# Atmega-SolderingStation-v2_7_2025-10-03.net
KiCad netlist of a schematic drawn in Altium Designer
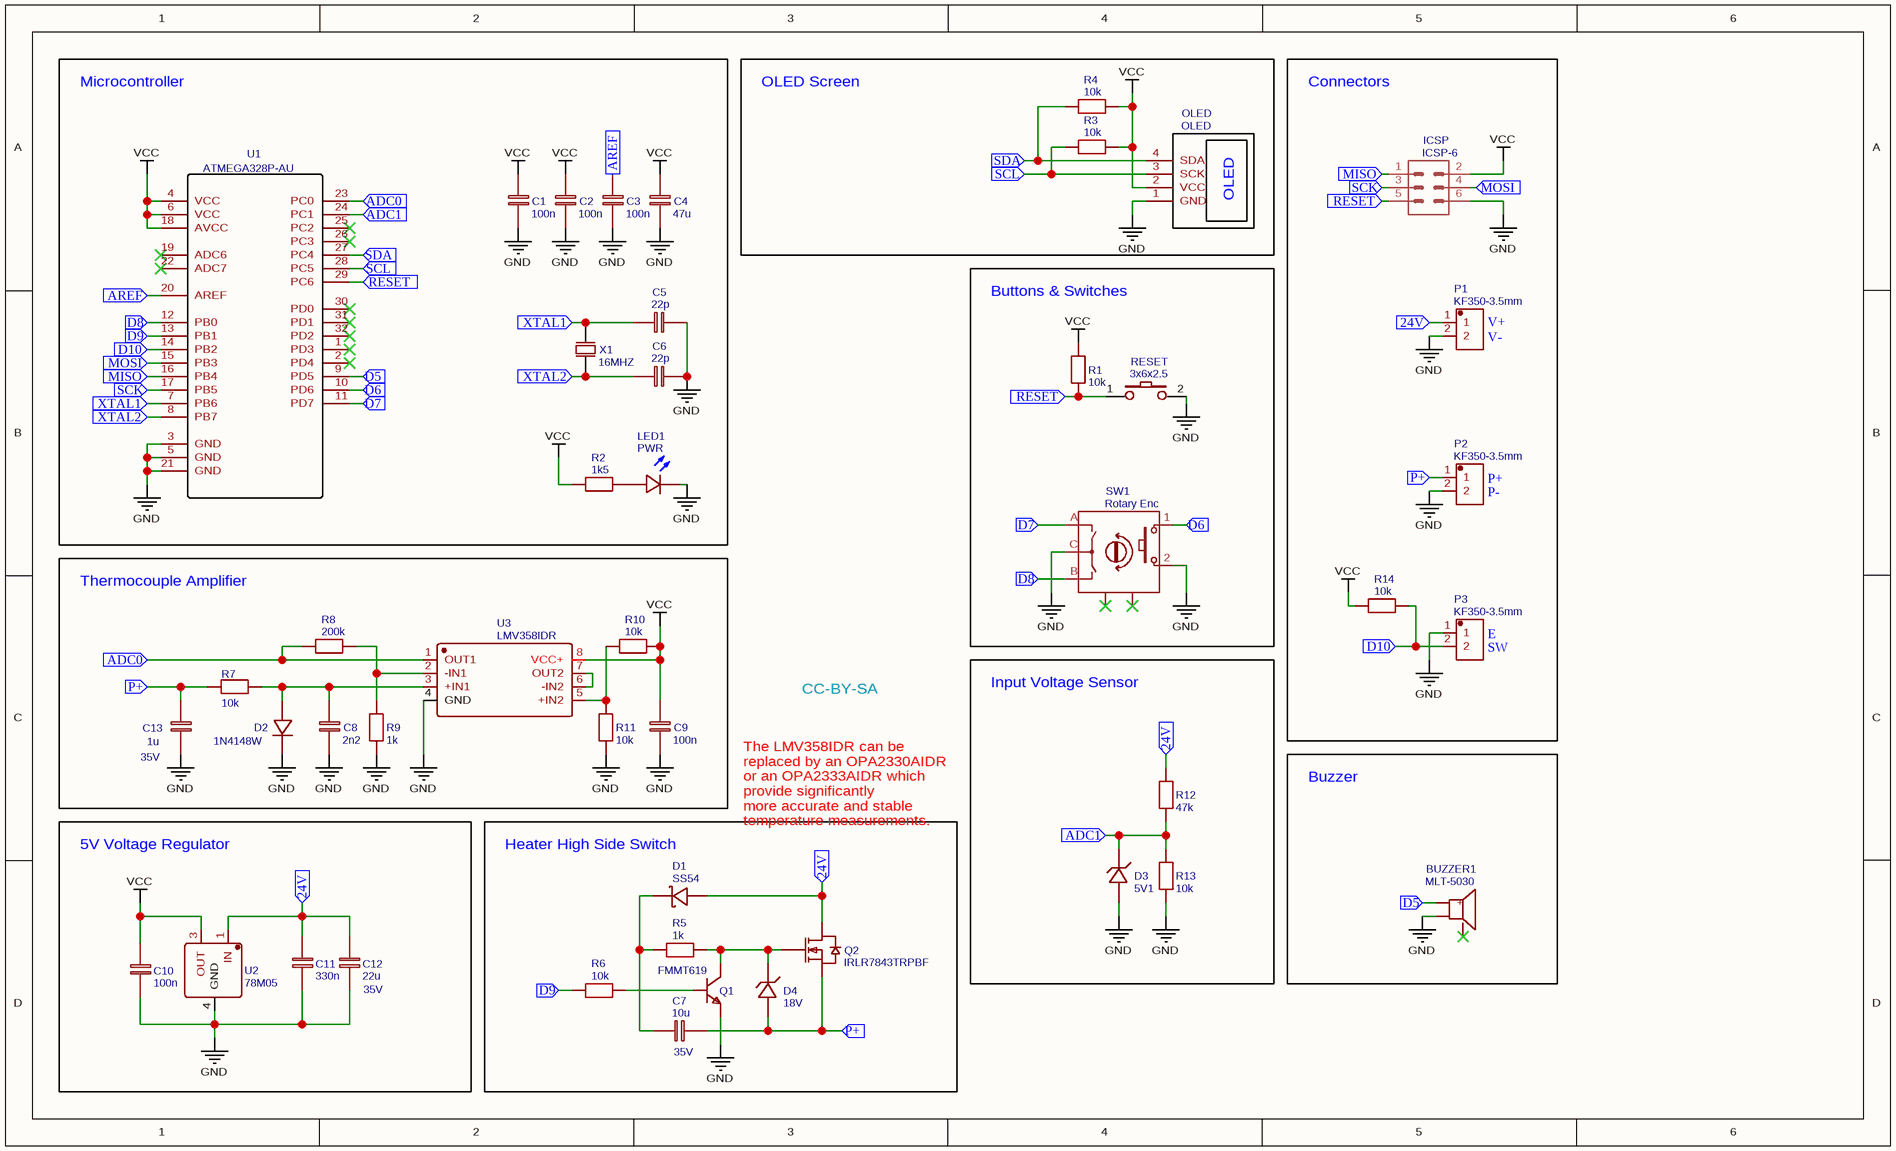
[diagram p0: Atmega-SolderingStation-v2.7_2025-10-03.schdoc]

(export (version "E")
  (design (tool "Eeschema 10.0.6"))
  (components
    (comp (ref "BUZZER1")
      (value "MLT-5030")
      (fields (field (name "MANUFACTURER") "HNDZ"))
      (libsource (lib "altium-import") (part "root_0_MLT-5030_"))
    )
    (comp (ref "C1")
      (value "100n")
      (fields (field (name "MANUFACTURER PART") "CC0603KRX7R9BB104") (field (name "MANUFACTURER") "YAGEO"))
      (libsource (lib "altium-import") (part "root_0_100n_"))
    )
    (comp (ref "C2")
      (value "100n")
      (fields (field (name "MANUFACTURER PART") "CC0603KRX7R9BB104") (field (name "MANUFACTURER") "YAGEO"))
      (libsource (lib "altium-import") (part "root_0_100n_"))
    )
    (comp (ref "C3")
      (value "100n")
      (fields (field (name "MANUFACTURER PART") "CC0603KRX7R9BB104") (field (name "MANUFACTURER") "YAGEO"))
      (libsource (lib "altium-import") (part "root_0_100n_"))
    )
    (comp (ref "C4")
      (value "47u")
      (fields (field (name "MANUFACTURER PART") "1206F476M100NT") (field (name "MANUFACTURER") "FH"))
      (libsource (lib "altium-import") (part "root_0_47u_"))
    )
    (comp (ref "C5")
      (value "22p")
      (fields (field (name "MANUFACTURER PART") "CL10C220JB8NNNC") (field (name "MANUFACTURER") "SAMSUNG"))
      (libsource (lib "altium-import") (part "root_1_22p_"))
    )
    (comp (ref "C6")
      (value "22p")
      (fields (field (name "MANUFACTURER PART") "CL10C220JB8NNNC") (field (name "MANUFACTURER") "SAMSUNG"))
      (libsource (lib "altium-import") (part "root_1_22p_"))
    )
    (comp (ref "C7")
      (value "10u")
      (fields
        (field (name "MANUFACTURER PART") "GMK316BJ106KL-T")
        (field (name "MANUFACTURER") "Taiyo Yuden")
      )
      (libsource (lib "altium-import") (part "root_1_10u_"))
    )
    (comp (ref "C8")
      (value "2n2")
      (fields (field (name "MANUFACTURER PART") "0603B222K500NT") (field (name "MANUFACTURER") "FH"))
      (libsource (lib "altium-import") (part "root_0_2n2_"))
    )
    (comp (ref "C9")
      (value "100n")
      (fields (field (name "MANUFACTURER PART") "CC0603KRX7R9BB104") (field (name "MANUFACTURER") "YAGEO"))
      (libsource (lib "altium-import") (part "root_0_100n_"))
    )
    (comp (ref "C10")
      (value "100n")
      (fields (field (name "MANUFACTURER PART") "CC0603KRX7R9BB104") (field (name "MANUFACTURER") "YAGEO"))
      (libsource (lib "altium-import") (part "root_0_100n_"))
    )
    (comp (ref "C11")
      (value "330n")
      (fields (field (name "MANUFACTURER PART") "C1608X7R1H334KT000E") (field (name "MANUFACTURER") "TDK"))
      (libsource (lib "altium-import") (part "root_0_330n_"))
    )
    (comp (ref "C12")
      (value "22u")
      (fields (field (name "MANUFACTURER PART") "C3216X5R1V226MTJ00E") (field (name "MANUFACTURER") "TDK"))
      (libsource (lib "altium-import") (part "root_0_22u_"))
    )
    (comp (ref "C13")
      (value "1u")
      (fields (field (name "MANUFACTURER PART") "CL10A105KB8NNNC") (field (name "MANUFACTURER") "SAMSUNG"))
      (libsource (lib "altium-import") (part "root_0_1u_"))
    )
    (comp (ref "D1")
      (value "SS54")
      (fields (field (name "MANUFACTURER") "Jingdao") (field (name "CONTRIBUTOR") "LCSC"))
      (libsource (lib "altium-import") (part "root_0_SS54_"))
    )
    (comp (ref "D2")
      (value "1N4148W")
      (fields
        (field (name "MANUFACTURER") "Vishay Intertech")
        (field (name "MANUFACTURER PART") "1N4148W-E3-08")
        (field (name "CONTRIBUTOR") "LCSC")
      )
      (libsource (lib "altium-import") (part "root_3_1N4148W_"))
    )
    (comp (ref "D3")
      (value "5V1")
      (fields
        (field (name "MANUFACTURER") "SEMTECH")
        (field (name "MANUFACTURER PART") "MM1Z5V1")
        (field (name "CONTRIBUTOR") "LCSC")
      )
      (libsource (lib "altium-import") (part "root_1_5V1_"))
    )
    (comp (ref "D4")
      (value "18V")
      (fields
        (field (name "MANUFACTURER") "Jingdao")
        (field (name "MANUFACTURER PART") "MM1Z18")
        (field (name "CONTRIBUTOR") "LCSC")
      )
      (libsource (lib "altium-import") (part "root_1_18V_"))
    )
    (comp (ref "ICSP")
      (value "ICSP-6")
      (fields (field (name "MANUFACTURER PART") "?") (field (name "CONTRIBUTOR") "DowntownCB"))
      (libsource (lib "altium-import") (part "root_2_ICSP-6_"))
    )
    (comp (ref "LED1")
      (value "PWR")
      (fields
        (field (name "MANUFACTURER") "EVERLIGHT")
        (field (name "MANUFACTURER PART") "19-217/BHC-ZL1M2RY/3T")
      )
      (libsource (lib "altium-import") (part "root_0_PWR_"))
    )
    (comp (ref "OLED")
      (value "OLED")
      (fields (field (name "MANUFACTURER PART") "SSD1306 I2C OLED") (field (name "CONTRIBUTOR") "stozk"))
      (libsource (lib "altium-import") (part "root_1_OLED_"))
    )
    (comp (ref "P1")
      (value "KF350-3.5mm")
      (fields (field (name "MANUFACTURER") "ReliaPro") (field (name "MANUFACTURER PART") "WJ2EDGVC-5.08-2P"))
      (libsource (lib "altium-import") (part "root_0_KF350-3.5mm_"))
    )
    (comp (ref "P2")
      (value "KF350-3.5mm")
      (fields (field (name "MANUFACTURER") "ReliaPro") (field (name "MANUFACTURER PART") "WJ2EDGVC-5.08-2P"))
      (libsource (lib "altium-import") (part "root_0_KF350-3.5mm_"))
    )
    (comp (ref "P3")
      (value "KF350-3.5mm")
      (fields (field (name "MANUFACTURER") "ReliaPro") (field (name "MANUFACTURER PART") "WJ2EDGVC-5.08-2P"))
      (libsource (lib "altium-import") (part "root_0_KF350-3.5mm_"))
    )
    (comp (ref "Q1")
      (value "FMMT619")
      (fields (field (name "MANUFACTURER") "CJ"))
      (libsource (lib "altium-import") (part "root_0_FMMT619_"))
    )
    (comp (ref "Q2")
      (value "IRLR7843TRPBF")
      (fields (field (name "MANUFACTURER") "IR"))
      (libsource (lib "altium-import") (part "root_0_IRLR7843TRPBF_"))
    )
    (comp (ref "R1")
      (value "10k")
      (fields (field (name "MANUFACTURER PART") "0603WAF1002T5E") (field (name "MANUFACTURER") "UniOhm"))
      (libsource (lib "altium-import") (part "root_1_10k_"))
    )
    (comp (ref "R2")
      (value "1k5")
      (fields (field (name "MANUFACTURER PART") "0603WAF1501T5E") (field (name "MANUFACTURER") "UniOhm"))
      (libsource (lib "altium-import") (part "root_0_1k5_"))
    )
    (comp (ref "R3")
      (value "10k")
      (fields (field (name "MANUFACTURER PART") "0603WAF1002T5E") (field (name "MANUFACTURER") "UniOhm"))
      (libsource (lib "altium-import") (part "root_0_10k_"))
    )
    (comp (ref "R4")
      (value "10k")
      (fields (field (name "MANUFACTURER PART") "0603WAF1002T5E") (field (name "MANUFACTURER") "UniOhm"))
      (libsource (lib "altium-import") (part "root_2_10k_"))
    )
    (comp (ref "R5")
      (value "1k")
      (fields (field (name "MANUFACTURER PART") "1206W4F1001T5E") (field (name "MANUFACTURER") "UniOhm"))
      (libsource (lib "altium-import") (part "root_0_1k_"))
    )
    (comp (ref "R6")
      (value "10k")
      (fields (field (name "MANUFACTURER PART") "0603WAF1002T5E") (field (name "MANUFACTURER") "UniOhm"))
      (libsource (lib "altium-import") (part "root_0_10k_"))
    )
    (comp (ref "R7")
      (value "10k")
      (fields (field (name "MANUFACTURER PART") "0603WAF1002T5E") (field (name "MANUFACTURER") "UniOhm"))
      (libsource (lib "altium-import") (part "root_0_10k_"))
    )
    (comp (ref "R8")
      (value "200k")
      (fields (field (name "MANUFACTURER PART") "0603WAF2003T5E") (field (name "MANUFACTURER") "UniOhm"))
      (libsource (lib "altium-import") (part "root_0_200k_"))
    )
    (comp (ref "R9")
      (value "1k")
      (fields (field (name "MANUFACTURER PART") "0603WAF1001T5E") (field (name "MANUFACTURER") "UniOhm"))
      (libsource (lib "altium-import") (part "root_1_1k_"))
    )
    (comp (ref "R10")
      (value "10k")
      (fields (field (name "MANUFACTURER PART") "0603WAF1002T5E") (field (name "MANUFACTURER") "UniOhm"))
      (libsource (lib "altium-import") (part "root_0_10k_"))
    )
    (comp (ref "R11")
      (value "10k")
      (fields (field (name "MANUFACTURER PART") "0603WAF1002T5E") (field (name "MANUFACTURER") "UniOhm"))
      (libsource (lib "altium-import") (part "root_1_10k_"))
    )
    (comp (ref "R12")
      (value "47k")
      (fields (field (name "MANUFACTURER PART") "0603WAF4702T5E") (field (name "MANUFACTURER") "UniOhm"))
      (libsource (lib "altium-import") (part "root_1_47k_"))
    )
    (comp (ref "R13")
      (value "10k")
      (fields (field (name "MANUFACTURER PART") "0603WAF1002T5E") (field (name "MANUFACTURER") "UniOhm"))
      (libsource (lib "altium-import") (part "root_1_10k_"))
    )
    (comp (ref "R14")
      (value "10k")
      (fields (field (name "MANUFACTURER PART") "0603WAF1002T5E") (field (name "MANUFACTURER") "UniOhm"))
      (libsource (lib "altium-import") (part "root_0_10k_"))
    )
    (comp (ref "RESET")
      (value "3x6x2.5")
      (fields
        (field (name "MANUFACTURER") "ReliaPro")
        (field (name "MANUFACTURER PART") "3x6x2.5Red head high temperature")
      )
      (libsource (lib "altium-import") (part "root_0_3x6x2.5_"))
    )
    (comp (ref "SW1")
      (value "Rotary Enc")
      (fields
        (field (name "MANUFACTURER") "BOURNS")
        (field (name "MANUFACTURER PART") "PEC11R-4015F-S0024")
        (field (name "CONTRIBUTOR") "LCSC")
      )
      (libsource (lib "altium-import") (part "root_0_Rotary Enc_"))
    )
    (comp (ref "U1")
      (value "ATMEGA328P-AU")
      (fields (field (name "MANUFACTURER") "MICROCHIP"))
      (libsource (lib "altium-import") (part "root_0_ATMEGA328P-AU_"))
    )
    (comp (ref "U2")
      (value "78M05")
      (fields (field (name "MANUFACTURER") "MICRONE") (field (name "MANUFACTURER PART") "ME78M05K3G"))
      (libsource (lib "altium-import") (part "root_3_78M05_"))
    )
    (comp (ref "U3")
      (value "LMV358IDR")
      (fields (field (name "MANUFACTURER") "TI"))
      (libsource (lib "altium-import") (part "root_0_LMV358IDR_"))
    )
    (comp (ref "X1")
      (value "16MHZ")
      (fields
        (field (name "MANUFACTURER") "Yangxing Tech")
        (field (name "MANUFACTURER PART") "X49SD16MSD2SI")
        (field (name "CONTRIBUTOR") "LCSC")
      )
      (libsource (lib "altium-import") (part "root_3_16MHZ_"))
    )
  )
  (nets
    (net (code "1") (name "/24V") (class "Default")
      (node (ref "C11") (pin "1") (pinfunction "1_1") (pintype "passive"))
      (node (ref "C12") (pin "1") (pinfunction "1_1") (pintype "passive"))
      (node (ref "D1") (pin "1") (pinfunction "A_1") (pintype "passive"))
      (node (ref "P1") (pin "1") (pinfunction "1_1") (pintype "passive"))
      (node (ref "Q2") (pin "4") (pinfunction "D_4") (pintype "passive"))
      (node (ref "R12") (pin "2") (pinfunction "2_2") (pintype "passive"))
      (node (ref "U2") (pin "1") (pinfunction "IN_1") (pintype "passive"))
    )
    (net (code "2") (name "/ADC0") (class "Default")
      (node (ref "R8") (pin "1") (pinfunction "1_1") (pintype "passive"))
      (node (ref "U1") (pin "23") (pinfunction "PC0_23") (pintype "passive"))
      (node (ref "U3") (pin "1") (pinfunction "OUT1_1") (pintype "passive"))
    )
    (net (code "3") (name "/ADC1") (class "Default")
      (node (ref "D3") (pin "2") (pinfunction "K_2") (pintype "passive"))
      (node (ref "R12") (pin "1") (pinfunction "1_1") (pintype "passive"))
      (node (ref "R13") (pin "2") (pinfunction "2_2") (pintype "passive"))
      (node (ref "U1") (pin "24") (pinfunction "PC1_24") (pintype "passive"))
    )
    (net (code "4") (name "/AREF") (class "Default")
      (node (ref "C3") (pin "1") (pinfunction "1_1") (pintype "passive"))
      (node (ref "U1") (pin "20") (pinfunction "AREF_20") (pintype "passive"))
    )
    (net (code "5") (name "/D5") (class "Default")
      (node (ref "BUZZER1") (pin "1") (pinfunction "+_1") (pintype "passive"))
      (node (ref "U1") (pin "9") (pinfunction "PD5_9") (pintype "passive"))
    )
    (net (code "6") (name "/D6") (class "Default")
      (node (ref "SW1") (pin "1") (pinfunction "1_1") (pintype "passive"))
      (node (ref "U1") (pin "10") (pinfunction "PD6_10") (pintype "passive"))
    )
    (net (code "7") (name "/D7") (class "Default")
      (node (ref "SW1") (pin "A") (pinfunction "A_A") (pintype "passive"))
      (node (ref "U1") (pin "11") (pinfunction "PD7_11") (pintype "passive"))
    )
    (net (code "8") (name "/D8") (class "Default")
      (node (ref "SW1") (pin "B") (pinfunction "B_B") (pintype "passive"))
      (node (ref "U1") (pin "12") (pinfunction "PB0_12") (pintype "passive"))
    )
    (net (code "9") (name "/D9") (class "Default")
      (node (ref "R6") (pin "1") (pinfunction "1_1") (pintype "passive"))
      (node (ref "U1") (pin "13") (pinfunction "PB1_13") (pintype "passive"))
    )
    (net (code "10") (name "/D10") (class "Default")
      (node (ref "P3") (pin "2") (pinfunction "2_2") (pintype "passive"))
      (node (ref "R14") (pin "2") (pinfunction "2_2") (pintype "passive"))
      (node (ref "U1") (pin "14") (pinfunction "PB2_14") (pintype "passive"))
    )
    (net (code "11") (name "/MISO") (class "Default")
      (node (ref "ICSP") (pin "1") (pinfunction "1_1") (pintype "passive"))
      (node (ref "U1") (pin "16") (pinfunction "PB4_16") (pintype "passive"))
    )
    (net (code "12") (name "/MOSI") (class "Default")
      (node (ref "ICSP") (pin "4") (pinfunction "4_4") (pintype "passive"))
      (node (ref "U1") (pin "15") (pinfunction "PB3_15") (pintype "passive"))
    )
    (net (code "13") (name "/P+") (class "Default")
      (node (ref "C13") (pin "1") (pinfunction "1_1") (pintype "passive"))
      (node (ref "C7") (pin "2") (pinfunction "2_2") (pintype "passive"))
      (node (ref "D4") (pin "1") (pinfunction "A_1") (pintype "passive"))
      (node (ref "P2") (pin "1") (pinfunction "1_1") (pintype "passive"))
      (node (ref "Q2") (pin "3") (pinfunction "S_3") (pintype "passive"))
      (node (ref "R7") (pin "1") (pinfunction "1_1") (pintype "passive"))
    )
    (net (code "14") (name "/RESET") (class "Default")
      (node (ref "ICSP") (pin "5") (pinfunction "5_5") (pintype "passive"))
      (node (ref "R1") (pin "1") (pinfunction "1_1") (pintype "passive"))
      (node (ref "RESET") (pin "1") (pinfunction "1_1") (pintype "passive"))
      (node (ref "U1") (pin "29") (pinfunction "PC6_29") (pintype "passive"))
    )
    (net (code "15") (name "/SCK") (class "Default")
      (node (ref "ICSP") (pin "3") (pinfunction "3_3") (pintype "passive"))
      (node (ref "U1") (pin "17") (pinfunction "PB5_17") (pintype "passive"))
    )
    (net (code "16") (name "/SCL") (class "Default")
      (node (ref "OLED") (pin "3") (pinfunction "SCK_3") (pintype "passive"))
      (node (ref "R3") (pin "1") (pinfunction "1_1") (pintype "passive"))
      (node (ref "U1") (pin "28") (pinfunction "PC5_28") (pintype "passive"))
    )
    (net (code "17") (name "/SDA") (class "Default")
      (node (ref "OLED") (pin "4") (pinfunction "SDA_4") (pintype "passive"))
      (node (ref "R4") (pin "2") (pinfunction "2_2") (pintype "passive"))
      (node (ref "U1") (pin "27") (pinfunction "PC4_27") (pintype "passive"))
    )
    (net (code "18") (name "/XTAL1") (class "Default")
      (node (ref "C5") (pin "1") (pinfunction "1_1") (pintype "passive"))
      (node (ref "U1") (pin "7") (pinfunction "PB6_7") (pintype "passive"))
      (node (ref "X1") (pin "2") (pinfunction "OSC2_2") (pintype "passive"))
    )
    (net (code "19") (name "/XTAL2") (class "Default")
      (node (ref "C6") (pin "1") (pinfunction "1_1") (pintype "passive"))
      (node (ref "U1") (pin "8") (pinfunction "PB7_8") (pintype "passive"))
      (node (ref "X1") (pin "1") (pinfunction "OSC1_1") (pintype "passive"))
    )
    (net (code "20") (name "GND") (class "Default")
      (node (ref "BUZZER1") (pin "2") (pinfunction "2_2") (pintype "passive"))
      (node (ref "C1") (pin "2") (pinfunction "2_2") (pintype "passive"))
      (node (ref "C10") (pin "2") (pinfunction "2_2") (pintype "passive"))
      (node (ref "C11") (pin "2") (pinfunction "2_2") (pintype "passive"))
      (node (ref "C12") (pin "2") (pinfunction "2_2") (pintype "passive"))
      (node (ref "C13") (pin "2") (pinfunction "2_2") (pintype "passive"))
      (node (ref "C2") (pin "2") (pinfunction "2_2") (pintype "passive"))
      (node (ref "C3") (pin "2") (pinfunction "2_2") (pintype "passive"))
      (node (ref "C4") (pin "2") (pinfunction "2_2") (pintype "passive"))
      (node (ref "C5") (pin "2") (pinfunction "2_2") (pintype "passive"))
      (node (ref "C6") (pin "2") (pinfunction "2_2") (pintype "passive"))
      (node (ref "C8") (pin "2") (pinfunction "2_2") (pintype "passive"))
      (node (ref "C9") (pin "2") (pinfunction "2_2") (pintype "passive"))
      (node (ref "D2") (pin "2") (pinfunction "K_2") (pintype "passive"))
      (node (ref "D3") (pin "1") (pinfunction "A_1") (pintype "passive"))
      (node (ref "ICSP") (pin "6") (pinfunction "6_6") (pintype "passive"))
      (node (ref "LED1") (pin "2") (pinfunction "-_2") (pintype "passive"))
      (node (ref "OLED") (pin "1") (pinfunction "GND_1") (pintype "passive"))
      (node (ref "P1") (pin "2") (pinfunction "2_2") (pintype "passive"))
      (node (ref "P2") (pin "2") (pinfunction "2_2") (pintype "passive"))
      (node (ref "P3") (pin "1") (pinfunction "1_1") (pintype "passive"))
      (node (ref "Q1") (pin "2") (pinfunction "E_2") (pintype "passive"))
      (node (ref "R11") (pin "1") (pinfunction "1_1") (pintype "passive"))
      (node (ref "R13") (pin "1") (pinfunction "1_1") (pintype "passive"))
      (node (ref "R9") (pin "1") (pinfunction "1_1") (pintype "passive"))
      (node (ref "RESET") (pin "2") (pinfunction "2_2") (pintype "passive"))
      (node (ref "SW1") (pin "2") (pinfunction "2_2") (pintype "passive"))
      (node (ref "SW1") (pin "C") (pinfunction "C_C") (pintype "passive"))
      (node (ref "U1") (pin "21") (pinfunction "GND_21") (pintype "passive"))
      (node (ref "U1") (pin "3") (pinfunction "GND_3") (pintype "passive"))
      (node (ref "U1") (pin "5") (pinfunction "GND_5") (pintype "passive"))
      (node (ref "U2") (pin "4") (pinfunction "GND_4") (pintype "passive"))
      (node (ref "U3") (pin "4") (pinfunction "GND_4") (pintype "passive"))
    )
    (net (code "21") (name "Net-(D1-K)") (class "Default")
      (node (ref "C7") (pin "1") (pinfunction "1_1") (pintype "passive"))
      (node (ref "D1") (pin "2") (pinfunction "K_2") (pintype "passive"))
      (node (ref "R5") (pin "1") (pinfunction "1_1") (pintype "passive"))
    )
    (net (code "22") (name "Net-(D2-A)") (class "Default")
      (node (ref "C8") (pin "1") (pinfunction "1_1") (pintype "passive"))
      (node (ref "D2") (pin "1") (pinfunction "A_1") (pintype "passive"))
      (node (ref "R7") (pin "2") (pinfunction "2_2") (pintype "passive"))
      (node (ref "U3") (pin "3") (pinfunction "+IN1_3") (pintype "passive"))
    )
    (net (code "23") (name "Net-(D4-K)") (class "Default")
      (node (ref "D4") (pin "2") (pinfunction "K_2") (pintype "passive"))
      (node (ref "Q1") (pin "3") (pinfunction "C_3") (pintype "passive"))
      (node (ref "Q2") (pin "1") (pinfunction "G_1") (pintype "passive"))
      (node (ref "R5") (pin "2") (pinfunction "2_2") (pintype "passive"))
    )
    (net (code "24") (name "Net-(LED1-+)") (class "Default")
      (node (ref "LED1") (pin "1") (pinfunction "+_1") (pintype "passive"))
      (node (ref "R2") (pin "2") (pinfunction "2_2") (pintype "passive"))
    )
    (net (code "25") (name "Net-(Q1-B)") (class "Default")
      (node (ref "Q1") (pin "1") (pinfunction "B_1") (pintype "passive"))
      (node (ref "R6") (pin "2") (pinfunction "2_2") (pintype "passive"))
    )
    (net (code "26") (name "Net-(U3-+IN2)") (class "Default")
      (node (ref "R10") (pin "1") (pinfunction "1_1") (pintype "passive"))
      (node (ref "R11") (pin "2") (pinfunction "2_2") (pintype "passive"))
      (node (ref "U3") (pin "5") (pinfunction "+IN2_5") (pintype "passive"))
    )
    (net (code "27") (name "Net-(U3--IN1)") (class "Default")
      (node (ref "R8") (pin "2") (pinfunction "2_2") (pintype "passive"))
      (node (ref "R9") (pin "2") (pinfunction "2_2") (pintype "passive"))
      (node (ref "U3") (pin "2") (pinfunction "-IN1_2") (pintype "passive"))
    )
    (net (code "28") (name "Net-(U3--IN2)") (class "Default")
      (node (ref "U3") (pin "6") (pinfunction "-IN2_6") (pintype "passive"))
      (node (ref "U3") (pin "7") (pinfunction "OUT2_7") (pintype "passive"))
    )
    (net (code "29") (name "VCC") (class "Default")
      (node (ref "C1") (pin "1") (pinfunction "1_1") (pintype "passive"))
      (node (ref "C10") (pin "1") (pinfunction "1_1") (pintype "passive"))
      (node (ref "C2") (pin "1") (pinfunction "1_1") (pintype "passive"))
      (node (ref "C4") (pin "1") (pinfunction "1_1") (pintype "passive"))
      (node (ref "C9") (pin "1") (pinfunction "1_1") (pintype "passive"))
      (node (ref "ICSP") (pin "2") (pinfunction "2_2") (pintype "passive"))
      (node (ref "OLED") (pin "2") (pinfunction "VCC_2") (pintype "passive"))
      (node (ref "R1") (pin "2") (pinfunction "2_2") (pintype "passive"))
      (node (ref "R10") (pin "2") (pinfunction "2_2") (pintype "passive"))
      (node (ref "R14") (pin "1") (pinfunction "1_1") (pintype "passive"))
      (node (ref "R2") (pin "1") (pinfunction "1_1") (pintype "passive"))
      (node (ref "R3") (pin "2") (pinfunction "2_2") (pintype "passive"))
      (node (ref "R4") (pin "1") (pinfunction "1_1") (pintype "passive"))
      (node (ref "U1") (pin "18") (pinfunction "AVCC_18") (pintype "passive"))
      (node (ref "U1") (pin "4") (pinfunction "VCC_4") (pintype "passive"))
      (node (ref "U1") (pin "6") (pinfunction "VCC_6") (pintype "passive"))
      (node (ref "U2") (pin "3") (pinfunction "OUT_3") (pintype "passive"))
      (node (ref "U3") (pin "8") (pinfunction "VCC+_8") (pintype "passive"))
    )
    (net (code "30") (name "unconnected-(BUZZER1-NC-Pad3)") (class "Default")
      (node (ref "BUZZER1") (pin "3") (pinfunction "NC_3") (pintype "passive+no_connect"))
    )
    (net (code "31") (name "unconnected-(SW1-PadMT1)") (class "Default")
      (node (ref "SW1") (pin "MT1") (pinfunction "MT1_MT1") (pintype "passive+no_connect"))
    )
    (net (code "32") (name "unconnected-(SW1-PadMT2)") (class "Default")
      (node (ref "SW1") (pin "MT2") (pinfunction "MT2_MT2") (pintype "passive+no_connect"))
    )
    (net (code "33") (name "unconnected-(U1-ADC6-Pad19)") (class "Default")
      (node (ref "U1") (pin "19") (pinfunction "ADC6_19") (pintype "passive+no_connect"))
    )
    (net (code "34") (name "unconnected-(U1-ADC7-Pad22)") (class "Default")
      (node (ref "U1") (pin "22") (pinfunction "ADC7_22") (pintype "passive+no_connect"))
    )
    (net (code "35") (name "unconnected-(U1-PC2-Pad25)") (class "Default")
      (node (ref "U1") (pin "25") (pinfunction "PC2_25") (pintype "passive+no_connect"))
    )
    (net (code "36") (name "unconnected-(U1-PC3-Pad26)") (class "Default")
      (node (ref "U1") (pin "26") (pinfunction "PC3_26") (pintype "passive+no_connect"))
    )
    (net (code "37") (name "unconnected-(U1-PD0-Pad30)") (class "Default")
      (node (ref "U1") (pin "30") (pinfunction "PD0_30") (pintype "passive+no_connect"))
    )
    (net (code "38") (name "unconnected-(U1-PD1-Pad31)") (class "Default")
      (node (ref "U1") (pin "31") (pinfunction "PD1_31") (pintype "passive+no_connect"))
    )
    (net (code "39") (name "unconnected-(U1-PD2-Pad32)") (class "Default")
      (node (ref "U1") (pin "32") (pinfunction "PD2_32") (pintype "passive+no_connect"))
    )
    (net (code "40") (name "unconnected-(U1-PD3-Pad1)") (class "Default")
      (node (ref "U1") (pin "1") (pinfunction "PD3_1") (pintype "passive+no_connect"))
    )
    (net (code "41") (name "unconnected-(U1-PD4-Pad2)") (class "Default")
      (node (ref "U1") (pin "2") (pinfunction "PD4_2") (pintype "passive+no_connect"))
    )
  )
)
